# board.net
KiCad netlist of a schematic drawn in EAGLE
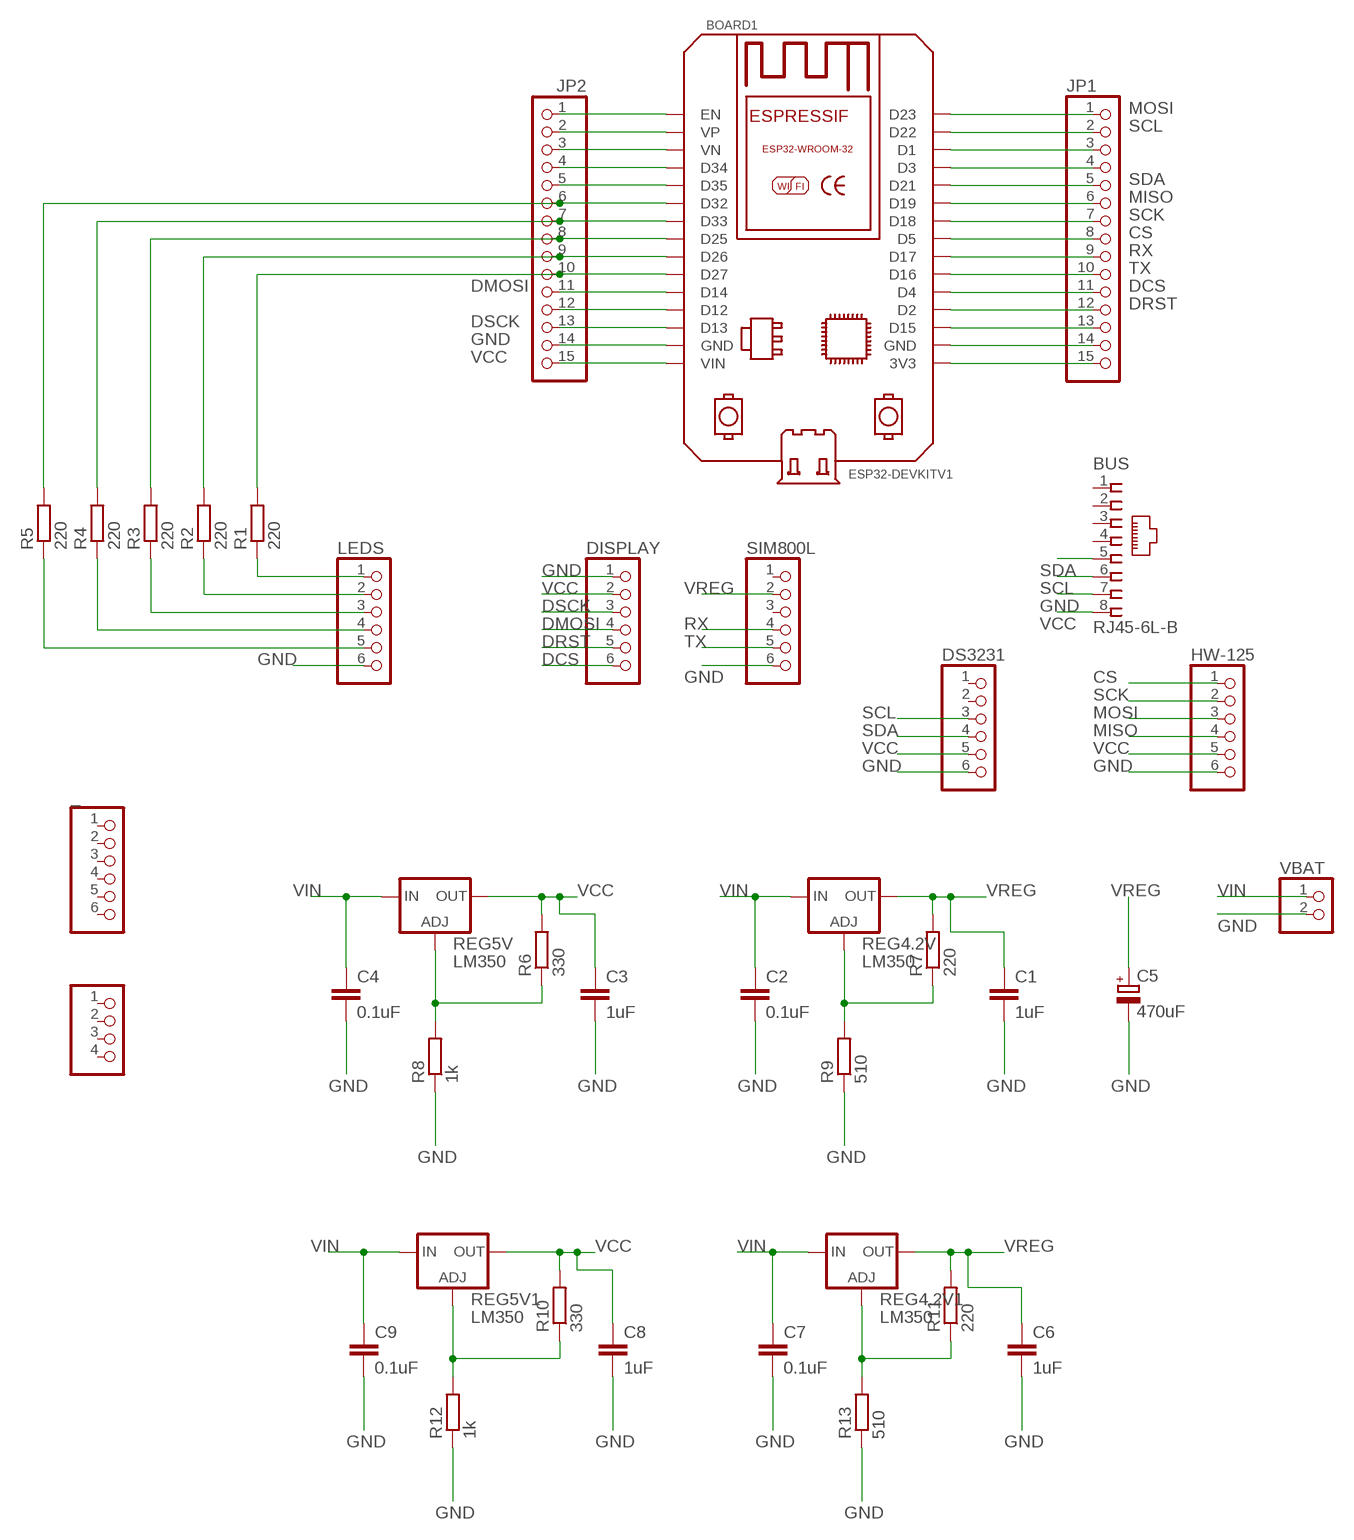
[diagram p0: schematic, sheet 1]

(export (version "E")
  (design (tool "Eeschema 10.0.6"))
  (components
    (comp (ref "BOARD1")
      (value "ESP32DEVKITV1")
      (footprint "eagle-import:ESP32-DEVKITV1")
      (libsource (lib "eagle-import") (part "ESP32DEVKITV1"))
    )
    (comp (ref "BUS")
      (value "RJ45-6L-B")
      (footprint "eagle-import:RJ45-NO-SHIELD")
      (libsource (lib "eagle-import") (part "RJ45-6L-B"))
    )
    (comp (ref "C1")
      (value "1uF")
      (footprint "eagle-import:C2.5-2")
      (libsource (lib "eagle-import") (part "C2.5/2"))
    )
    (comp (ref "C2")
      (value "0.1uF")
      (footprint "eagle-import:C2.5-2")
      (libsource (lib "eagle-import") (part "C2.5/2"))
    )
    (comp (ref "C3")
      (value "1uF")
      (footprint "eagle-import:C2.5-2")
      (libsource (lib "eagle-import") (part "C2.5/2"))
    )
    (comp (ref "C4")
      (value "0.1uF")
      (footprint "eagle-import:C2.5-2")
      (libsource (lib "eagle-import") (part "C2.5/2"))
    )
    (comp (ref "C5")
      (value "470uF")
      (footprint "eagle-import:E3,5-8")
      (libsource (lib "eagle-import") (part "CPOL-EUE3.5-8"))
    )
    (comp (ref "C6")
      (value "1uF")
      (footprint "eagle-import:C2.5-2")
      (libsource (lib "eagle-import") (part "C2.5/2"))
    )
    (comp (ref "C7")
      (value "0.1uF")
      (footprint "eagle-import:C2.5-2")
      (libsource (lib "eagle-import") (part "C2.5/2"))
    )
    (comp (ref "C8")
      (value "1uF")
      (footprint "eagle-import:C2.5-2")
      (libsource (lib "eagle-import") (part "C2.5/2"))
    )
    (comp (ref "C9")
      (value "0.1uF")
      (footprint "eagle-import:C2.5-2")
      (libsource (lib "eagle-import") (part "C2.5/2"))
    )
    (comp (ref "DISPLAY")
      (value "PINHD-1X6")
      (footprint "eagle-import:1X06")
      (libsource (lib "eagle-import") (part "PINHD-1X6"))
    )
    (comp (ref "DS3231")
      (value "PINHD-1X6")
      (footprint "eagle-import:1X06")
      (libsource (lib "eagle-import") (part "PINHD-1X6"))
    )
    (comp (ref "HW-125")
      (value "PINHD-1X6")
      (footprint "eagle-import:1X06")
      (libsource (lib "eagle-import") (part "PINHD-1X6"))
    )
    (comp (ref "JP1")
      (value "PINHD-1X15")
      (footprint "eagle-import:1X15")
      (libsource (lib "eagle-import") (part "PINHD-1X15"))
    )
    (comp (ref "JP2")
      (value "PINHD-1X15")
      (footprint "eagle-import:1X15")
      (libsource (lib "eagle-import") (part "PINHD-1X15"))
    )
    (comp (ref "JP3")
      (value "PINHD-1X4")
      (footprint "eagle-import:1X04")
      (libsource (lib "eagle-import") (part "PINHD-1X4"))
    )
    (comp (ref "LEDS")
      (value "PINHD-1X6")
      (footprint "eagle-import:1X06")
      (libsource (lib "eagle-import") (part "PINHD-1X6"))
    )
    (comp (ref "R1")
      (value "220")
      (footprint "eagle-import:R1206")
      (libsource (lib "eagle-import") (part "R-EU_R1206"))
    )
    (comp (ref "R2")
      (value "220")
      (footprint "eagle-import:R1206")
      (libsource (lib "eagle-import") (part "R-EU_R1206"))
    )
    (comp (ref "R3")
      (value "220")
      (footprint "eagle-import:R1206")
      (libsource (lib "eagle-import") (part "R-EU_R1206"))
    )
    (comp (ref "R4")
      (value "220")
      (footprint "eagle-import:R1206")
      (libsource (lib "eagle-import") (part "R-EU_R1206"))
    )
    (comp (ref "R5")
      (value "220")
      (footprint "eagle-import:R1206")
      (libsource (lib "eagle-import") (part "R-EU_R1206"))
    )
    (comp (ref "R6")
      (value "330")
      (footprint "eagle-import:0204_7")
      (libsource (lib "eagle-import") (part "R-EU_0204/7"))
    )
    (comp (ref "R7")
      (value "220")
      (footprint "eagle-import:0204_7")
      (libsource (lib "eagle-import") (part "R-EU_0204/7"))
    )
    (comp (ref "R8")
      (value "1k")
      (footprint "eagle-import:0204_7")
      (libsource (lib "eagle-import") (part "R-EU_0204/7"))
    )
    (comp (ref "R9")
      (value "510")
      (footprint "eagle-import:0204_7")
      (libsource (lib "eagle-import") (part "R-EU_0204/7"))
    )
    (comp (ref "R10")
      (value "330")
      (footprint "eagle-import:0204_7")
      (libsource (lib "eagle-import") (part "R-EU_0204/7"))
    )
    (comp (ref "R11")
      (value "220")
      (footprint "eagle-import:0204_7")
      (libsource (lib "eagle-import") (part "R-EU_0204/7"))
    )
    (comp (ref "R12")
      (value "1k")
      (footprint "eagle-import:0204_7")
      (libsource (lib "eagle-import") (part "R-EU_0204/7"))
    )
    (comp (ref "R13")
      (value "510")
      (footprint "eagle-import:0204_7")
      (libsource (lib "eagle-import") (part "R-EU_0204/7"))
    )
    (comp (ref "REG4.2V")
      (value "LM350")
      (footprint "eagle-import:317TS")
      (libsource (lib "eagle-import") (part "LM317TS"))
    )
    (comp (ref "REG4.2V1")
      (value "LM350")
      (footprint "eagle-import:317TS")
      (libsource (lib "eagle-import") (part "LM317TS"))
    )
    (comp (ref "REG5V")
      (value "LM350")
      (footprint "eagle-import:317TS")
      (libsource (lib "eagle-import") (part "LM317TS"))
    )
    (comp (ref "REG5V1")
      (value "LM350")
      (footprint "eagle-import:317TS")
      (libsource (lib "eagle-import") (part "LM317TS"))
    )
    (comp (ref "SIM800L")
      (value "PINHD-1X6")
      (footprint "eagle-import:1X06")
      (libsource (lib "eagle-import") (part "PINHD-1X6"))
    )
    (comp (ref "VBAT")
      (value "PINHD-1X2")
      (footprint "eagle-import:1X02")
      (libsource (lib "eagle-import") (part "PINHD-1X2"))
    )
    (comp (ref "_")
      (value "PINHD-1X6")
      (footprint "eagle-import:1X06")
      (libsource (lib "eagle-import") (part "PINHD-1X6"))
    )
  )
  (nets
    (net (code "1") (name "/CS") (class "Default")
      (node (ref "BOARD1") (pin "D5") (pinfunction "D5_D5") (pintype "bidirectional"))
      (node (ref "HW-125") (pin "1") (pinfunction "1_1") (pintype "passive"))
      (node (ref "JP1") (pin "8") (pinfunction "8_8") (pintype "passive"))
    )
    (net (code "2") (name "/DCS") (class "Default")
      (node (ref "BOARD1") (pin "D4") (pinfunction "D4_D4") (pintype "bidirectional"))
      (node (ref "DISPLAY") (pin "6") (pinfunction "6_6") (pintype "passive"))
      (node (ref "JP1") (pin "11") (pinfunction "11_11") (pintype "passive"))
    )
    (net (code "3") (name "/DMOSI") (class "Default")
      (node (ref "BOARD1") (pin "D14") (pinfunction "D14_D14") (pintype "bidirectional"))
      (node (ref "DISPLAY") (pin "4") (pinfunction "4_4") (pintype "passive"))
      (node (ref "JP2") (pin "11") (pinfunction "11_11") (pintype "passive"))
    )
    (net (code "4") (name "/DRST") (class "Default")
      (node (ref "BOARD1") (pin "D2") (pinfunction "D2_D2") (pintype "bidirectional"))
      (node (ref "DISPLAY") (pin "5") (pinfunction "5_5") (pintype "passive"))
      (node (ref "JP1") (pin "12") (pinfunction "12_12") (pintype "passive"))
    )
    (net (code "5") (name "/DSCK") (class "Default")
      (node (ref "BOARD1") (pin "D13") (pinfunction "D13_D13") (pintype "bidirectional"))
      (node (ref "DISPLAY") (pin "3") (pinfunction "3_3") (pintype "passive"))
      (node (ref "JP2") (pin "13") (pinfunction "13_13") (pintype "passive"))
    )
    (net (code "6") (name "/GND") (class "Default")
      (node (ref "BOARD1") (pin "GND") (pinfunction "GND_GND") (pintype "bidirectional"))
      (node (ref "BUS") (pin "7") (pinfunction "7_7") (pintype "passive"))
      (node (ref "C1") (pin "2") (pinfunction "2_2") (pintype "passive"))
      (node (ref "C2") (pin "2") (pinfunction "2_2") (pintype "passive"))
      (node (ref "C3") (pin "2") (pinfunction "2_2") (pintype "passive"))
      (node (ref "C4") (pin "2") (pinfunction "2_2") (pintype "passive"))
      (node (ref "C5") (pin "-") (pinfunction "-_-") (pintype "passive"))
      (node (ref "C6") (pin "2") (pinfunction "2_2") (pintype "passive"))
      (node (ref "C7") (pin "2") (pinfunction "2_2") (pintype "passive"))
      (node (ref "C8") (pin "2") (pinfunction "2_2") (pintype "passive"))
      (node (ref "C9") (pin "2") (pinfunction "2_2") (pintype "passive"))
      (node (ref "DISPLAY") (pin "1") (pinfunction "1_1") (pintype "passive"))
      (node (ref "DS3231") (pin "6") (pinfunction "6_6") (pintype "passive"))
      (node (ref "HW-125") (pin "6") (pinfunction "6_6") (pintype "passive"))
      (node (ref "JP2") (pin "14") (pinfunction "14_14") (pintype "passive"))
      (node (ref "LEDS") (pin "6") (pinfunction "6_6") (pintype "passive"))
      (node (ref "R12") (pin "1") (pinfunction "1_1") (pintype "passive"))
      (node (ref "R13") (pin "1") (pinfunction "1_1") (pintype "passive"))
      (node (ref "R8") (pin "1") (pinfunction "1_1") (pintype "passive"))
      (node (ref "R9") (pin "1") (pinfunction "1_1") (pintype "passive"))
      (node (ref "SIM800L") (pin "6") (pinfunction "6_6") (pintype "passive"))
      (node (ref "VBAT") (pin "2") (pinfunction "2_2") (pintype "passive"))
    )
    (net (code "7") (name "/MISO") (class "Default")
      (node (ref "BOARD1") (pin "D19") (pinfunction "D19_D19") (pintype "bidirectional"))
      (node (ref "HW-125") (pin "4") (pinfunction "4_4") (pintype "passive"))
      (node (ref "JP1") (pin "6") (pinfunction "6_6") (pintype "passive"))
    )
    (net (code "8") (name "/MOSI") (class "Default")
      (node (ref "BOARD1") (pin "D23") (pinfunction "D23_D23") (pintype "bidirectional"))
      (node (ref "HW-125") (pin "3") (pinfunction "3_3") (pintype "passive"))
      (node (ref "JP1") (pin "1") (pinfunction "1_1") (pintype "passive"))
    )
    (net (code "9") (name "/RX") (class "Default")
      (node (ref "BOARD1") (pin "D17") (pinfunction "D17_D17") (pintype "bidirectional"))
      (node (ref "JP1") (pin "9") (pinfunction "9_9") (pintype "passive"))
      (node (ref "SIM800L") (pin "4") (pinfunction "4_4") (pintype "passive"))
    )
    (net (code "10") (name "/SCK") (class "Default")
      (node (ref "BOARD1") (pin "D18") (pinfunction "D18_D18") (pintype "bidirectional"))
      (node (ref "HW-125") (pin "2") (pinfunction "2_2") (pintype "passive"))
      (node (ref "JP1") (pin "7") (pinfunction "7_7") (pintype "passive"))
    )
    (net (code "11") (name "/SCL") (class "Default")
      (node (ref "BOARD1") (pin "D22") (pinfunction "D22_D22") (pintype "bidirectional"))
      (node (ref "BUS") (pin "6") (pinfunction "6_6") (pintype "passive"))
      (node (ref "DS3231") (pin "3") (pinfunction "3_3") (pintype "passive"))
      (node (ref "JP1") (pin "2") (pinfunction "2_2") (pintype "passive"))
    )
    (net (code "12") (name "/SDA") (class "Default")
      (node (ref "BOARD1") (pin "D21") (pinfunction "D21_D21") (pintype "bidirectional"))
      (node (ref "BUS") (pin "5") (pinfunction "5_5") (pintype "passive"))
      (node (ref "DS3231") (pin "4") (pinfunction "4_4") (pintype "passive"))
      (node (ref "JP1") (pin "5") (pinfunction "5_5") (pintype "passive"))
    )
    (net (code "13") (name "/TX") (class "Default")
      (node (ref "BOARD1") (pin "D16") (pinfunction "D16_D16") (pintype "bidirectional"))
      (node (ref "JP1") (pin "10") (pinfunction "10_10") (pintype "passive"))
      (node (ref "SIM800L") (pin "5") (pinfunction "5_5") (pintype "passive"))
    )
    (net (code "14") (name "/VCC") (class "Default")
      (node (ref "BOARD1") (pin "VIN") (pinfunction "VIN_VIN") (pintype "bidirectional"))
      (node (ref "BUS") (pin "8") (pinfunction "8_8") (pintype "passive"))
      (node (ref "C3") (pin "1") (pinfunction "1_1") (pintype "passive"))
      (node (ref "C8") (pin "1") (pinfunction "1_1") (pintype "passive"))
      (node (ref "DISPLAY") (pin "2") (pinfunction "2_2") (pintype "passive"))
      (node (ref "DS3231") (pin "5") (pinfunction "5_5") (pintype "passive"))
      (node (ref "HW-125") (pin "5") (pinfunction "5_5") (pintype "passive"))
      (node (ref "JP2") (pin "15") (pinfunction "15_15") (pintype "passive"))
      (node (ref "R10") (pin "2") (pinfunction "2_2") (pintype "passive"))
      (node (ref "R6") (pin "2") (pinfunction "2_2") (pintype "passive"))
      (node (ref "REG5V") (pin "2") (pinfunction "OUT_2") (pintype "passive"))
      (node (ref "REG5V1") (pin "2") (pinfunction "OUT_2") (pintype "passive"))
    )
    (net (code "15") (name "/VIN") (class "Default")
      (node (ref "C2") (pin "1") (pinfunction "1_1") (pintype "passive"))
      (node (ref "C4") (pin "1") (pinfunction "1_1") (pintype "passive"))
      (node (ref "C7") (pin "1") (pinfunction "1_1") (pintype "passive"))
      (node (ref "C9") (pin "1") (pinfunction "1_1") (pintype "passive"))
      (node (ref "REG4.2V") (pin "3") (pinfunction "IN_3") (pintype "input"))
      (node (ref "REG4.2V1") (pin "3") (pinfunction "IN_3") (pintype "input"))
      (node (ref "REG5V") (pin "3") (pinfunction "IN_3") (pintype "input"))
      (node (ref "REG5V1") (pin "3") (pinfunction "IN_3") (pintype "input"))
      (node (ref "VBAT") (pin "1") (pinfunction "1_1") (pintype "passive"))
    )
    (net (code "16") (name "/VREG") (class "Default")
      (node (ref "C1") (pin "1") (pinfunction "1_1") (pintype "passive"))
      (node (ref "C5") (pin "+") (pinfunction "+_+") (pintype "passive"))
      (node (ref "C6") (pin "1") (pinfunction "1_1") (pintype "passive"))
      (node (ref "R11") (pin "2") (pinfunction "2_2") (pintype "passive"))
      (node (ref "R7") (pin "2") (pinfunction "2_2") (pintype "passive"))
      (node (ref "REG4.2V") (pin "2") (pinfunction "OUT_2") (pintype "passive"))
      (node (ref "REG4.2V1") (pin "2") (pinfunction "OUT_2") (pintype "passive"))
      (node (ref "SIM800L") (pin "2") (pinfunction "2_2") (pintype "passive"))
    )
    (net (code "17") (name "Net-(BOARD1-GND-PadGND@1)") (class "Default")
      (node (ref "BOARD1") (pin "GND@1") (pinfunction "GND_GND@1") (pintype "bidirectional"))
      (node (ref "JP1") (pin "14") (pinfunction "14_14") (pintype "passive"))
    )
    (net (code "18") (name "Net-(BOARD1-Pad3V3)") (class "Default")
      (node (ref "BOARD1") (pin "3V3") (pinfunction "3V3_3V3") (pintype "bidirectional"))
      (node (ref "JP1") (pin "15") (pinfunction "15_15") (pintype "passive"))
    )
    (net (code "19") (name "Net-(BOARD1-PadD1)") (class "Default")
      (node (ref "BOARD1") (pin "D1") (pinfunction "D1_D1") (pintype "bidirectional"))
      (node (ref "JP1") (pin "3") (pinfunction "3_3") (pintype "passive"))
    )
    (net (code "20") (name "Net-(BOARD1-PadD3)") (class "Default")
      (node (ref "BOARD1") (pin "D3") (pinfunction "D3_D3") (pintype "bidirectional"))
      (node (ref "JP1") (pin "4") (pinfunction "4_4") (pintype "passive"))
    )
    (net (code "21") (name "Net-(BOARD1-PadD12)") (class "Default")
      (node (ref "BOARD1") (pin "D12") (pinfunction "D12_D12") (pintype "bidirectional"))
      (node (ref "JP2") (pin "12") (pinfunction "12_12") (pintype "passive"))
    )
    (net (code "22") (name "Net-(BOARD1-PadD15)") (class "Default")
      (node (ref "BOARD1") (pin "D15") (pinfunction "D15_D15") (pintype "bidirectional"))
      (node (ref "JP1") (pin "13") (pinfunction "13_13") (pintype "passive"))
    )
    (net (code "23") (name "Net-(BOARD1-PadD25)") (class "Default")
      (node (ref "BOARD1") (pin "D25") (pinfunction "D25_D25") (pintype "bidirectional"))
      (node (ref "JP2") (pin "8") (pinfunction "8_8") (pintype "passive"))
      (node (ref "R3") (pin "2") (pinfunction "2_2") (pintype "passive"))
    )
    (net (code "24") (name "Net-(BOARD1-PadD26)") (class "Default")
      (node (ref "BOARD1") (pin "D26") (pinfunction "D26_D26") (pintype "bidirectional"))
      (node (ref "JP2") (pin "9") (pinfunction "9_9") (pintype "passive"))
      (node (ref "R2") (pin "2") (pinfunction "2_2") (pintype "passive"))
    )
    (net (code "25") (name "Net-(BOARD1-PadD27)") (class "Default")
      (node (ref "BOARD1") (pin "D27") (pinfunction "D27_D27") (pintype "bidirectional"))
      (node (ref "JP2") (pin "10") (pinfunction "10_10") (pintype "passive"))
      (node (ref "R1") (pin "2") (pinfunction "2_2") (pintype "passive"))
    )
    (net (code "26") (name "Net-(BOARD1-PadD32)") (class "Default")
      (node (ref "BOARD1") (pin "D32") (pinfunction "D32_D32") (pintype "bidirectional"))
      (node (ref "JP2") (pin "6") (pinfunction "6_6") (pintype "passive"))
      (node (ref "R5") (pin "2") (pinfunction "2_2") (pintype "passive"))
    )
    (net (code "27") (name "Net-(BOARD1-PadD33)") (class "Default")
      (node (ref "BOARD1") (pin "D33") (pinfunction "D33_D33") (pintype "bidirectional"))
      (node (ref "JP2") (pin "7") (pinfunction "7_7") (pintype "passive"))
      (node (ref "R4") (pin "2") (pinfunction "2_2") (pintype "passive"))
    )
    (net (code "28") (name "Net-(BOARD1-PadD34)") (class "Default")
      (node (ref "BOARD1") (pin "D34") (pinfunction "D34_D34") (pintype "bidirectional"))
      (node (ref "JP2") (pin "4") (pinfunction "4_4") (pintype "passive"))
    )
    (net (code "29") (name "Net-(BOARD1-PadD35)") (class "Default")
      (node (ref "BOARD1") (pin "D35") (pinfunction "D35_D35") (pintype "bidirectional"))
      (node (ref "JP2") (pin "5") (pinfunction "5_5") (pintype "passive"))
    )
    (net (code "30") (name "Net-(BOARD1-PadEN)") (class "Default")
      (node (ref "BOARD1") (pin "EN") (pinfunction "EN_EN") (pintype "bidirectional"))
      (node (ref "JP2") (pin "1") (pinfunction "1_1") (pintype "passive"))
    )
    (net (code "31") (name "Net-(BOARD1-PadVN)") (class "Default")
      (node (ref "BOARD1") (pin "VN") (pinfunction "VN_VN") (pintype "bidirectional"))
      (node (ref "JP2") (pin "3") (pinfunction "3_3") (pintype "passive"))
    )
    (net (code "32") (name "Net-(BOARD1-PadVP)") (class "Default")
      (node (ref "BOARD1") (pin "VP") (pinfunction "VP_VP") (pintype "bidirectional"))
      (node (ref "JP2") (pin "2") (pinfunction "2_2") (pintype "passive"))
    )
    (net (code "33") (name "Net-(LEDS-Pad1)") (class "Default")
      (node (ref "LEDS") (pin "1") (pinfunction "1_1") (pintype "passive"))
      (node (ref "R1") (pin "1") (pinfunction "1_1") (pintype "passive"))
    )
    (net (code "34") (name "Net-(LEDS-Pad2)") (class "Default")
      (node (ref "LEDS") (pin "2") (pinfunction "2_2") (pintype "passive"))
      (node (ref "R2") (pin "1") (pinfunction "1_1") (pintype "passive"))
    )
    (net (code "35") (name "Net-(LEDS-Pad3)") (class "Default")
      (node (ref "LEDS") (pin "3") (pinfunction "3_3") (pintype "passive"))
      (node (ref "R3") (pin "1") (pinfunction "1_1") (pintype "passive"))
    )
    (net (code "36") (name "Net-(LEDS-Pad4)") (class "Default")
      (node (ref "LEDS") (pin "4") (pinfunction "4_4") (pintype "passive"))
      (node (ref "R4") (pin "1") (pinfunction "1_1") (pintype "passive"))
    )
    (net (code "37") (name "Net-(LEDS-Pad5)") (class "Default")
      (node (ref "LEDS") (pin "5") (pinfunction "5_5") (pintype "passive"))
      (node (ref "R5") (pin "1") (pinfunction "1_1") (pintype "passive"))
    )
    (net (code "38") (name "Net-(REG4.2V-ADJ)") (class "Default")
      (node (ref "R7") (pin "1") (pinfunction "1_1") (pintype "passive"))
      (node (ref "R9") (pin "2") (pinfunction "2_2") (pintype "passive"))
      (node (ref "REG4.2V") (pin "1") (pinfunction "ADJ_1") (pintype "input"))
    )
    (net (code "39") (name "Net-(REG4.2V1-ADJ)") (class "Default")
      (node (ref "R11") (pin "1") (pinfunction "1_1") (pintype "passive"))
      (node (ref "R13") (pin "2") (pinfunction "2_2") (pintype "passive"))
      (node (ref "REG4.2V1") (pin "1") (pinfunction "ADJ_1") (pintype "input"))
    )
    (net (code "40") (name "Net-(REG5V-ADJ)") (class "Default")
      (node (ref "R6") (pin "1") (pinfunction "1_1") (pintype "passive"))
      (node (ref "R8") (pin "2") (pinfunction "2_2") (pintype "passive"))
      (node (ref "REG5V") (pin "1") (pinfunction "ADJ_1") (pintype "input"))
    )
    (net (code "41") (name "Net-(REG5V1-ADJ)") (class "Default")
      (node (ref "R10") (pin "1") (pinfunction "1_1") (pintype "passive"))
      (node (ref "R12") (pin "2") (pinfunction "2_2") (pintype "passive"))
      (node (ref "REG5V1") (pin "1") (pinfunction "ADJ_1") (pintype "input"))
    )
    (net (code "42") (name "unconnected-(BUS-Pad1)") (class "Default")
      (node (ref "BUS") (pin "1") (pinfunction "1_1") (pintype "passive"))
    )
    (net (code "43") (name "unconnected-(BUS-Pad2)") (class "Default")
      (node (ref "BUS") (pin "2") (pinfunction "2_2") (pintype "passive"))
    )
    (net (code "44") (name "unconnected-(BUS-Pad3)") (class "Default")
      (node (ref "BUS") (pin "3") (pinfunction "3_3") (pintype "passive"))
    )
    (net (code "45") (name "unconnected-(BUS-Pad4)") (class "Default")
      (node (ref "BUS") (pin "4") (pinfunction "4_4") (pintype "passive"))
    )
    (net (code "46") (name "unconnected-(DS3231-Pad1)") (class "Default")
      (node (ref "DS3231") (pin "1") (pinfunction "1_1") (pintype "passive"))
    )
    (net (code "47") (name "unconnected-(DS3231-Pad2)") (class "Default")
      (node (ref "DS3231") (pin "2") (pinfunction "2_2") (pintype "passive"))
    )
    (net (code "48") (name "unconnected-(JP3-Pad1)") (class "Default")
      (node (ref "JP3") (pin "1") (pinfunction "1_1") (pintype "passive"))
    )
    (net (code "49") (name "unconnected-(JP3-Pad2)") (class "Default")
      (node (ref "JP3") (pin "2") (pinfunction "2_2") (pintype "passive"))
    )
    (net (code "50") (name "unconnected-(JP3-Pad3)") (class "Default")
      (node (ref "JP3") (pin "3") (pinfunction "3_3") (pintype "passive"))
    )
    (net (code "51") (name "unconnected-(JP3-Pad4)") (class "Default")
      (node (ref "JP3") (pin "4") (pinfunction "4_4") (pintype "passive"))
    )
    (net (code "52") (name "unconnected-(SIM800L-Pad1)") (class "Default")
      (node (ref "SIM800L") (pin "1") (pinfunction "1_1") (pintype "passive"))
    )
    (net (code "53") (name "unconnected-(SIM800L-Pad3)") (class "Default")
      (node (ref "SIM800L") (pin "3") (pinfunction "3_3") (pintype "passive"))
    )
    (net (code "54") (name "unconnected-(_-Pad1)") (class "Default")
      (node (ref "_") (pin "1") (pinfunction "1_1") (pintype "passive"))
    )
    (net (code "55") (name "unconnected-(_-Pad2)") (class "Default")
      (node (ref "_") (pin "2") (pinfunction "2_2") (pintype "passive"))
    )
    (net (code "56") (name "unconnected-(_-Pad3)") (class "Default")
      (node (ref "_") (pin "3") (pinfunction "3_3") (pintype "passive"))
    )
    (net (code "57") (name "unconnected-(_-Pad4)") (class "Default")
      (node (ref "_") (pin "4") (pinfunction "4_4") (pintype "passive"))
    )
    (net (code "58") (name "unconnected-(_-Pad5)") (class "Default")
      (node (ref "_") (pin "5") (pinfunction "5_5") (pintype "passive"))
    )
    (net (code "59") (name "unconnected-(_-Pad6)") (class "Default")
      (node (ref "_") (pin "6") (pinfunction "6_6") (pintype "passive"))
    )
  )
)
